# preparedinstruments_0_bechemel_v12_KEYPA.net
KiCad netlist of a schematic drawn in EAGLE
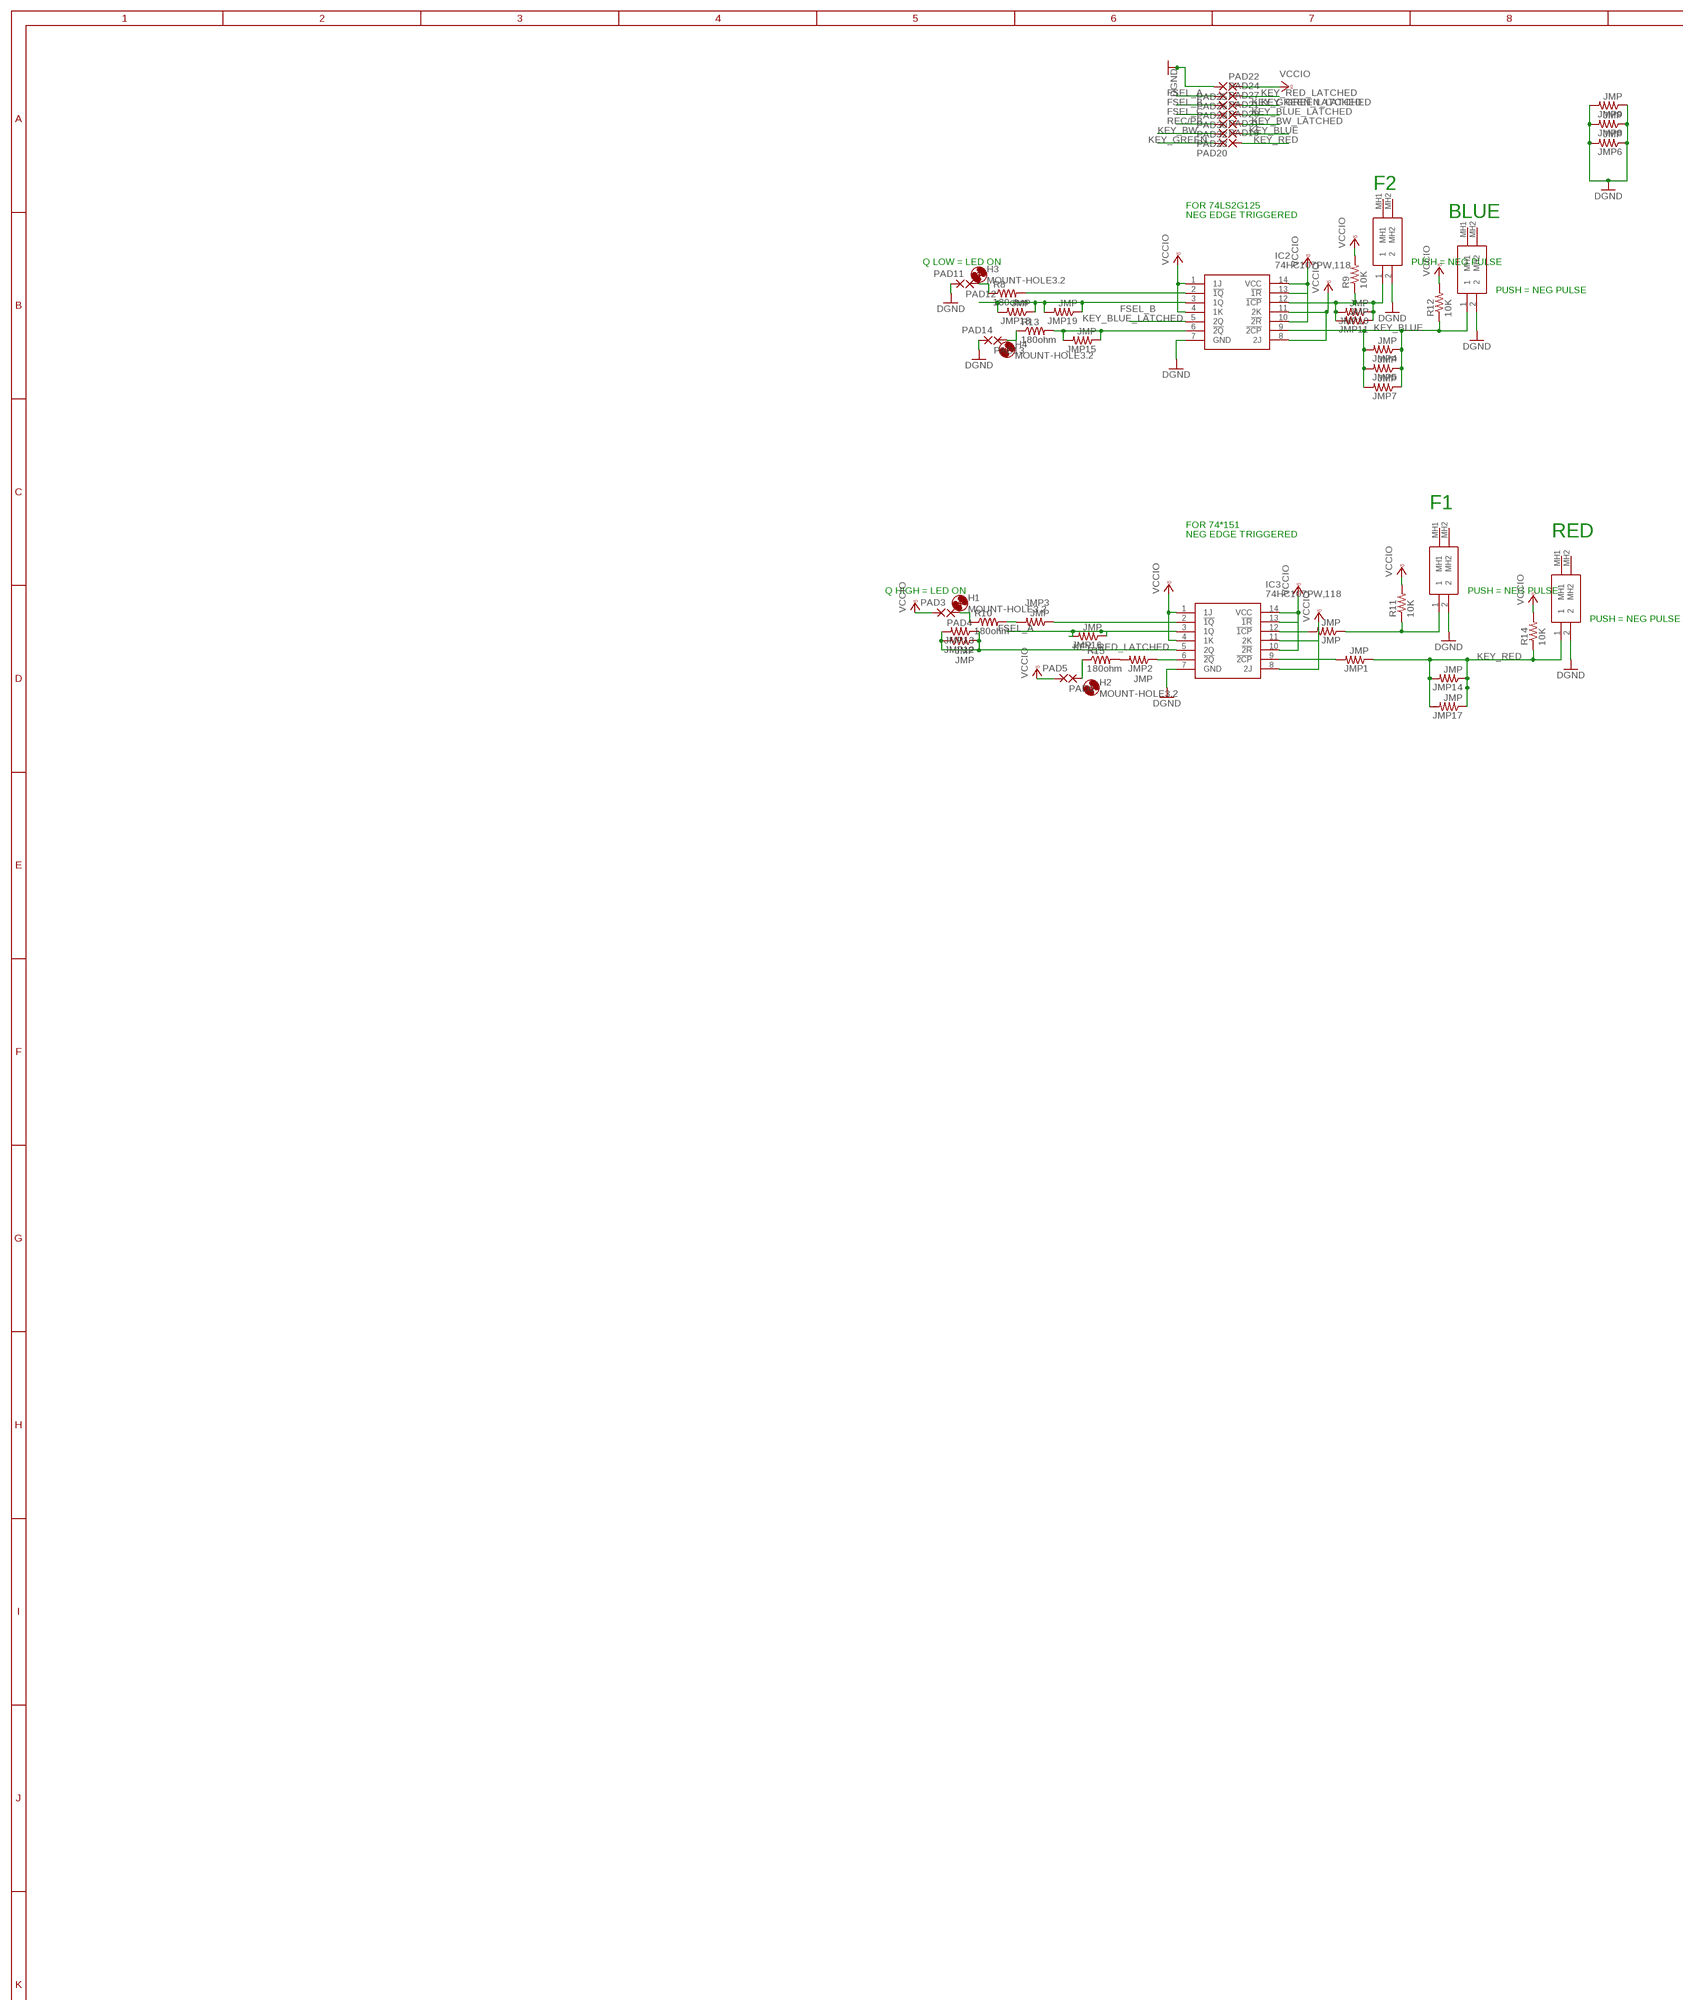
[diagram p0: schematic, sheet 1, part 1 of 3]
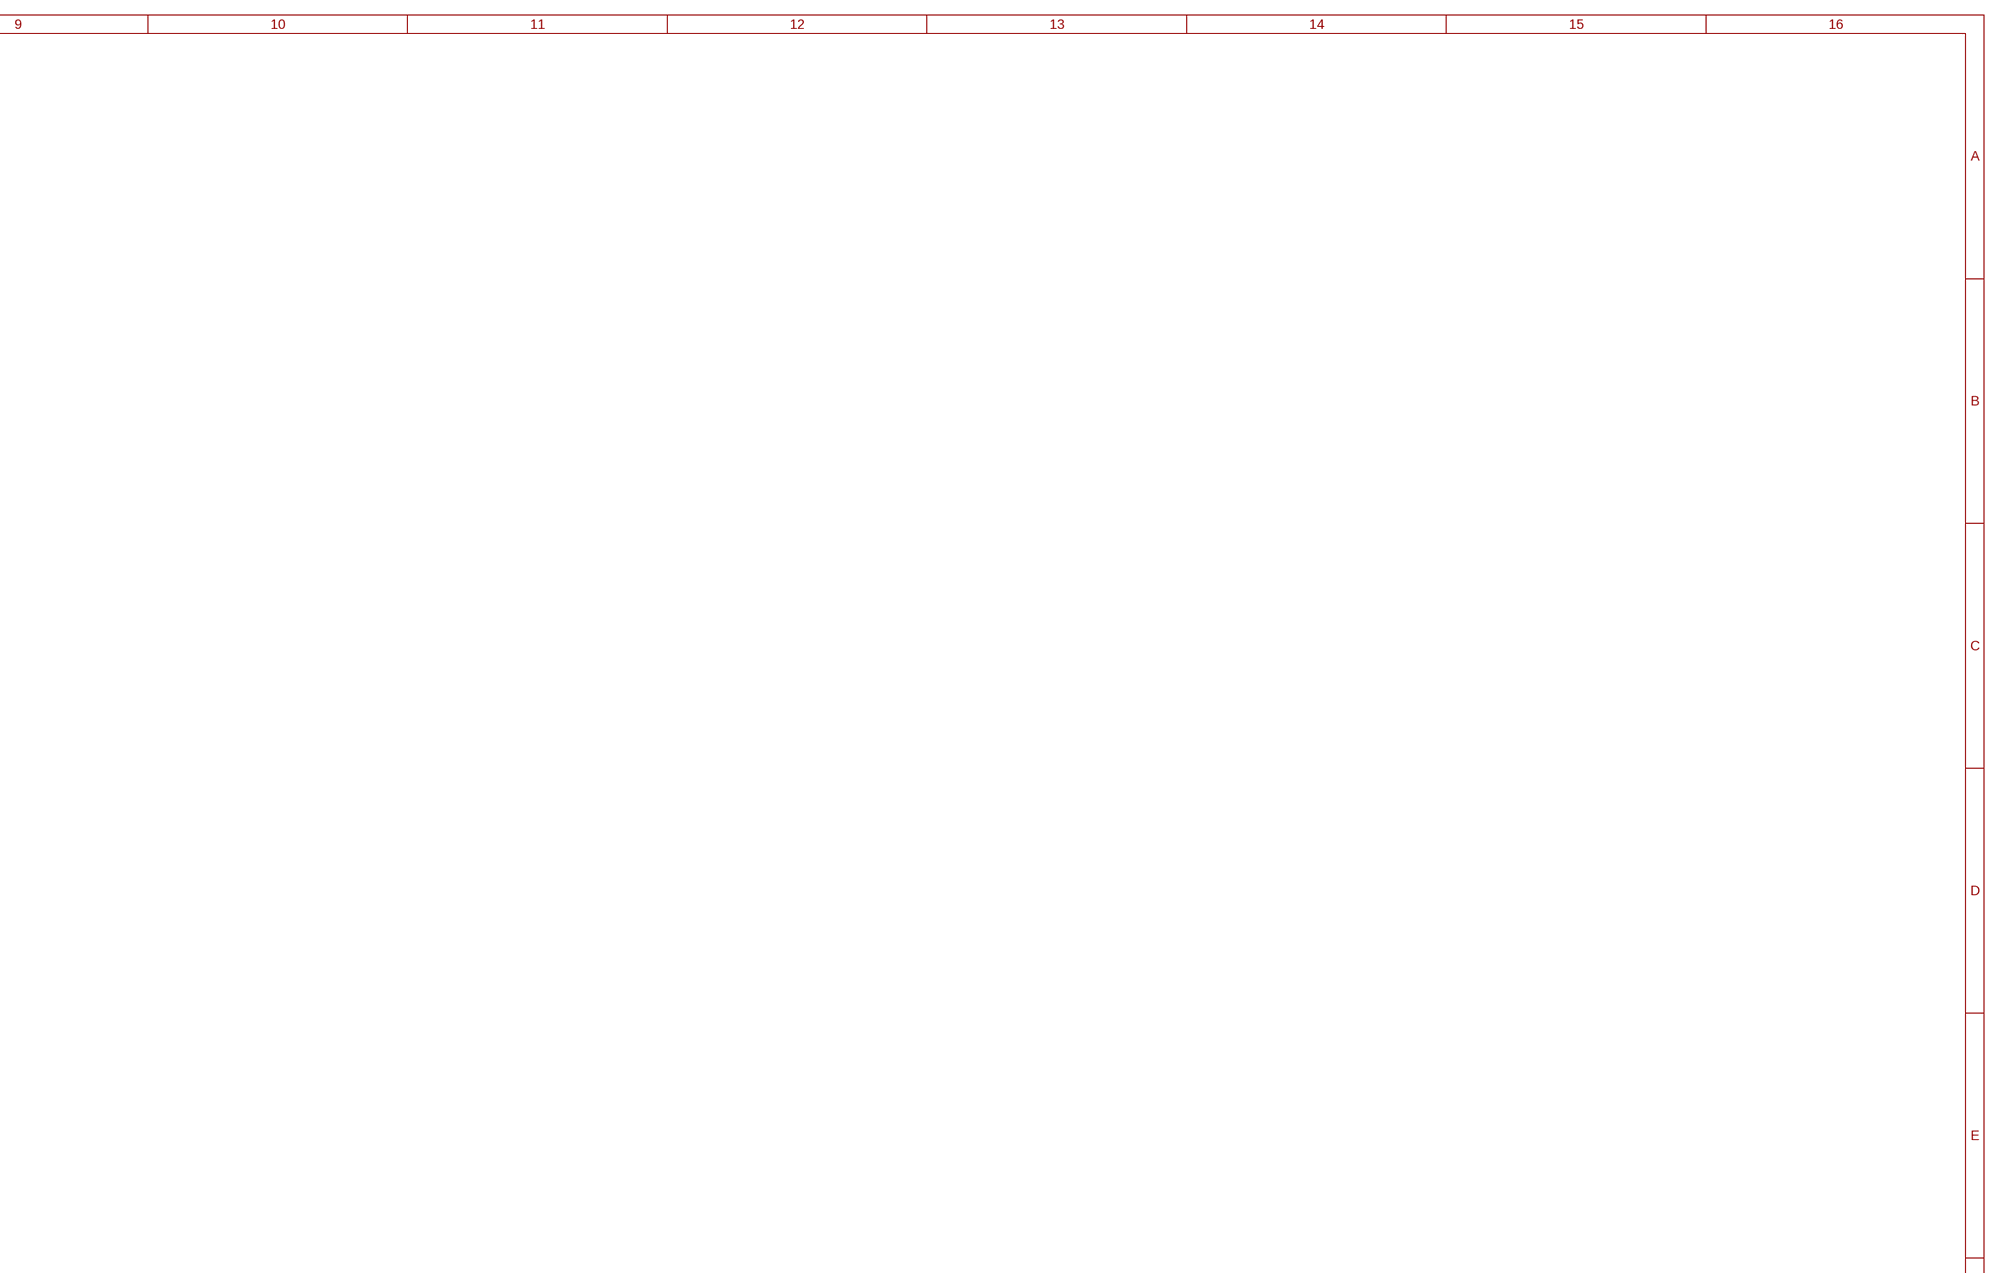
[diagram p1: schematic, sheet 1, part 2 of 3]
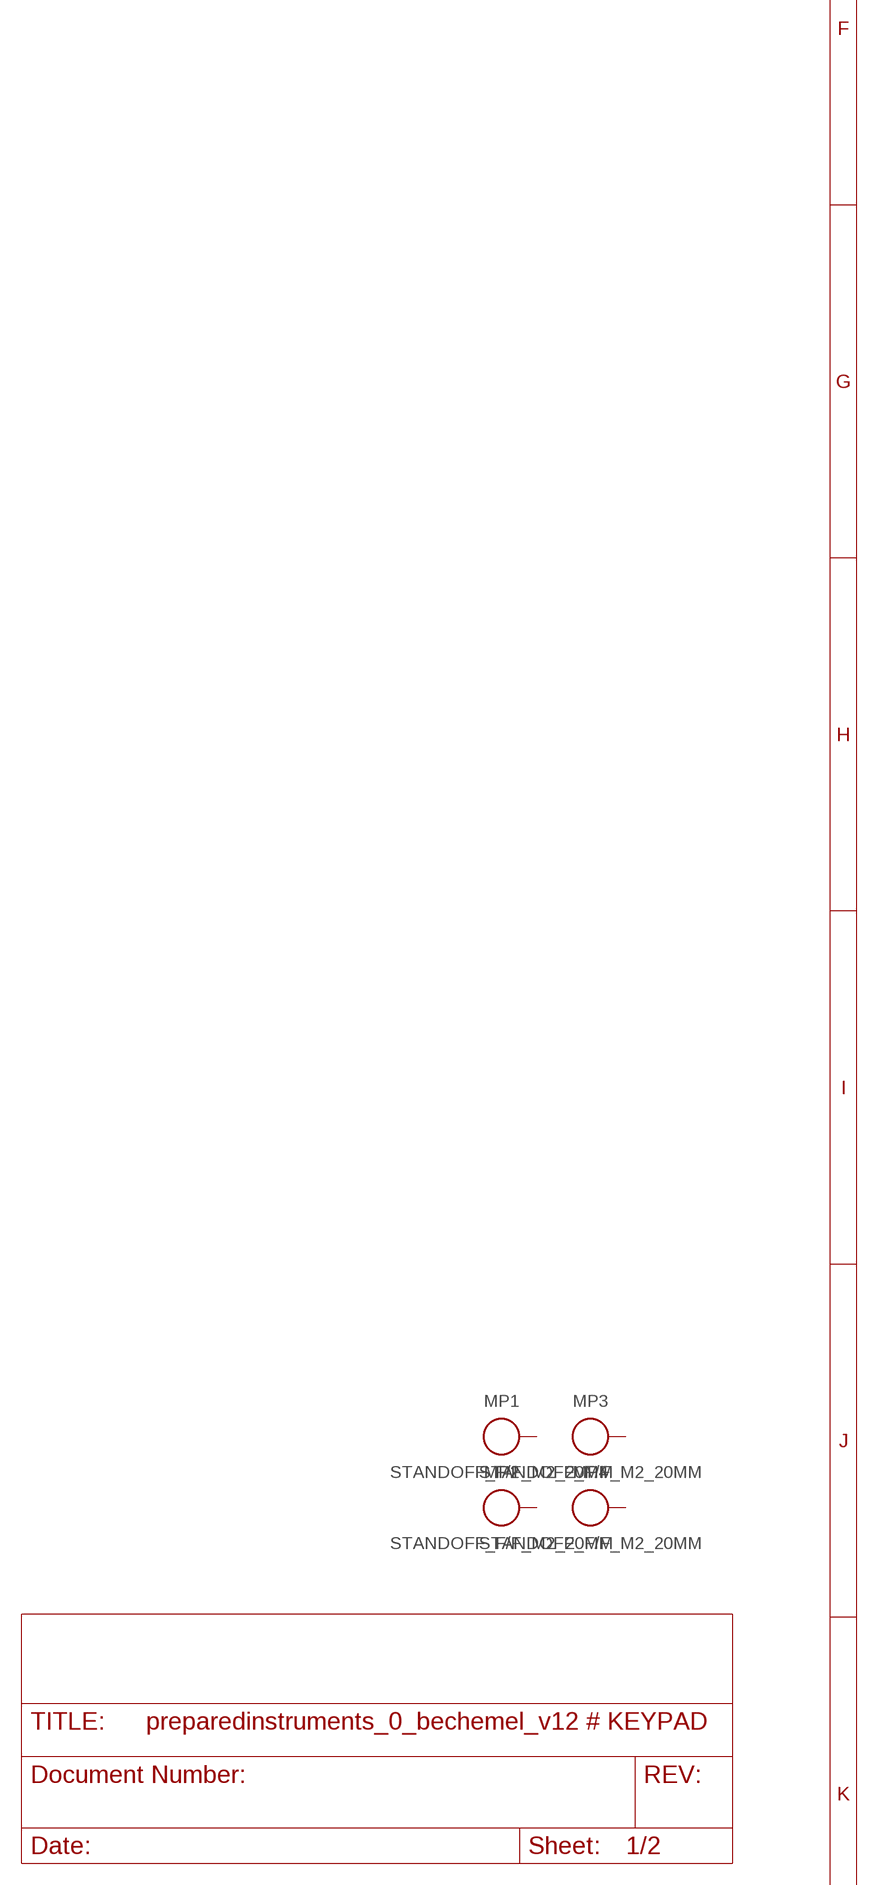
[diagram p2: schematic, sheet 1, part 3 of 3]
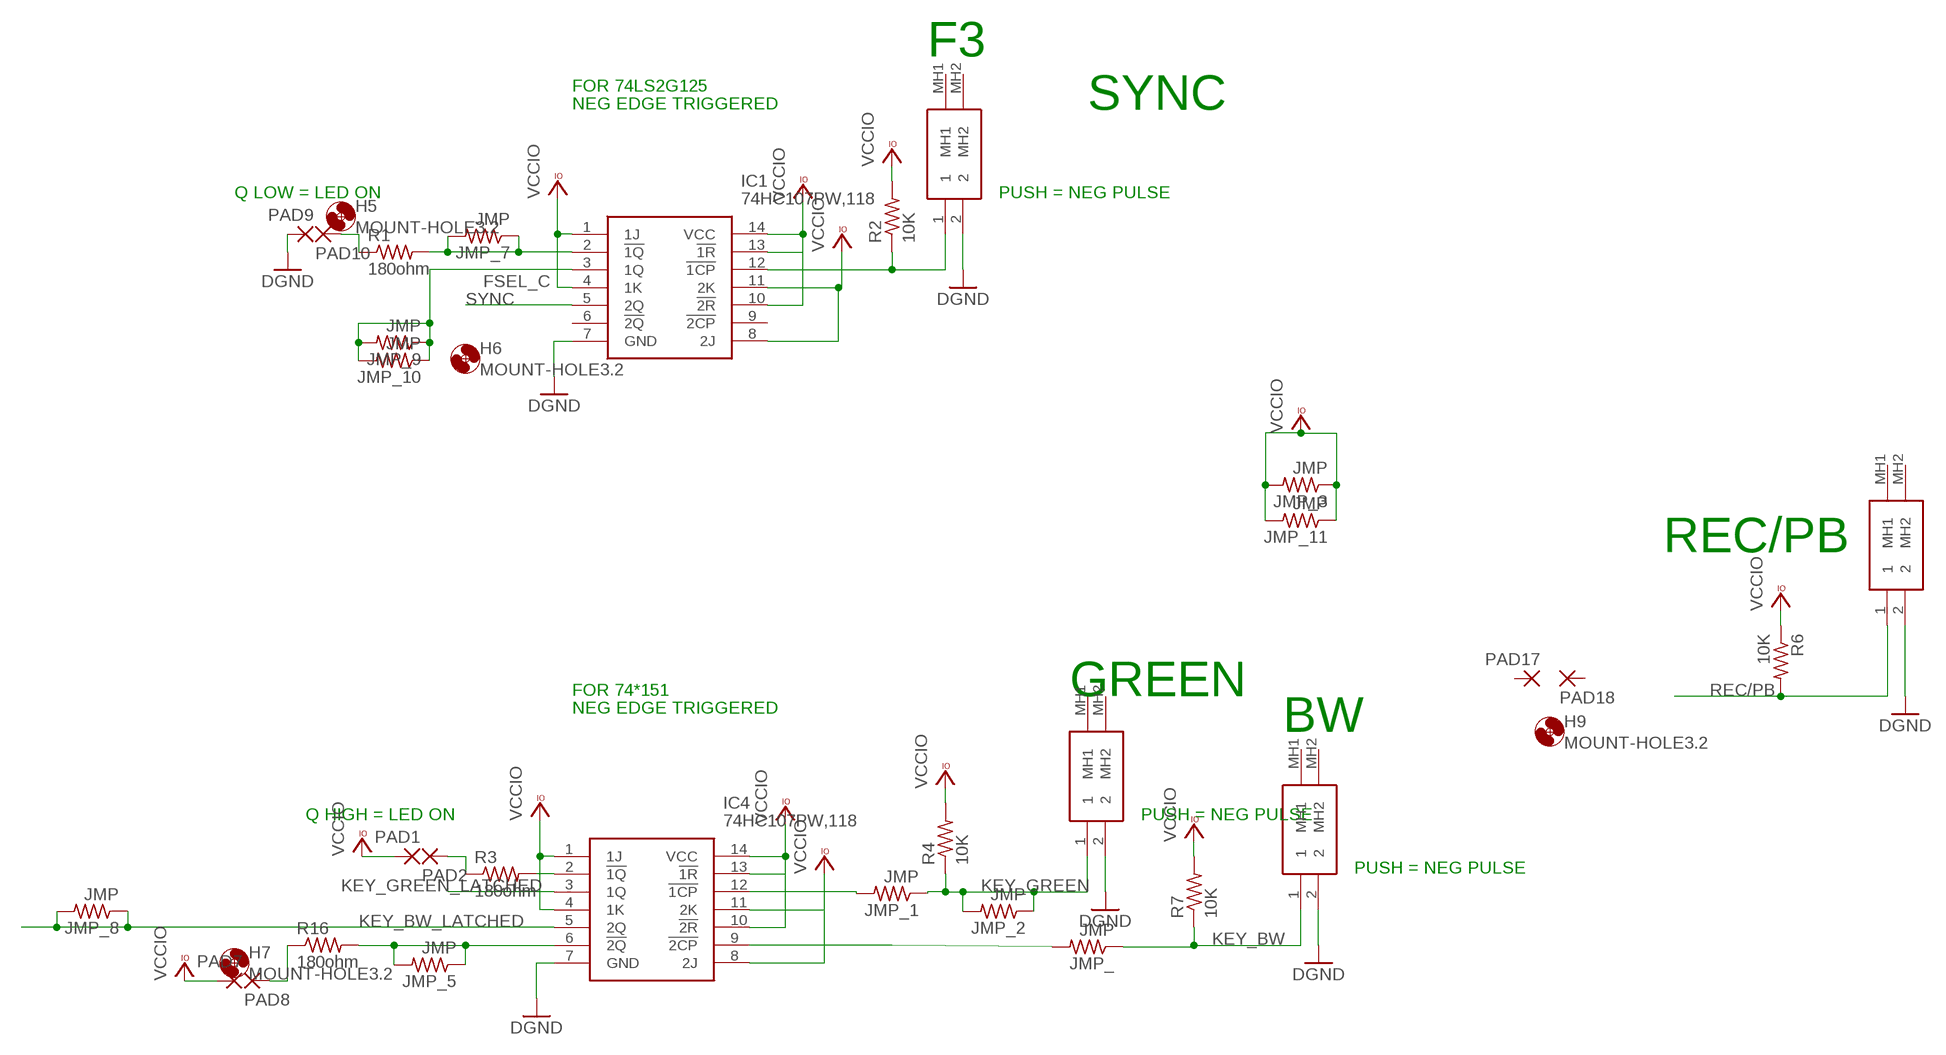
[diagram p3: schematic, sheet 2]

(export (version "E")
  (design (tool "Eeschema 10.0.6"))
  (components
    (comp (ref "H5")
      (value "MOUNT-HOLE3.2")
      (footprint "eagle-import:3,2")
      (libsource (lib "eagle-import") (part "MOUNT-HOLE3.2"))
    )
    (comp (ref "H6")
      (value "MOUNT-HOLE3.2")
      (footprint "eagle-import:3,2")
      (libsource (lib "eagle-import") (part "MOUNT-HOLE3.2"))
    )
    (comp (ref "H7")
      (value "MOUNT-HOLE3.2")
      (footprint "eagle-import:3,2")
      (libsource (lib "eagle-import") (part "MOUNT-HOLE3.2"))
    )
    (comp (ref "H9")
      (value "MOUNT-HOLE3.2")
      (footprint "eagle-import:3,2")
      (libsource (lib "eagle-import") (part "MOUNT-HOLE3.2"))
    )
    (comp (ref "IC1")
      (value "74HC107PW,118")
      (footprint "eagle-import:SOP65P640X110-14N")
      (fields (field (name "MOUSER_PART_NUMBER") "771-HC107PW118"))
      (libsource (lib "eagle-import") (part "74HC107PW,118"))
    )
    (comp (ref "IC4")
      (value "74HC107PW,118")
      (footprint "eagle-import:SOP65P640X110-14N")
      (fields (field (name "MOUSER_PART_NUMBER") "771-HC107PW118"))
      (libsource (lib "eagle-import") (part "74HC107PW,118"))
    )
    (comp (ref "JMP_")
      (value "JMP")
      (footprint "eagle-import:R0805")
      (libsource (lib "eagle-import") (part "R-US_R0805"))
    )
    (comp (ref "JMP_1")
      (value "JMP")
      (footprint "eagle-import:R0805")
      (libsource (lib "eagle-import") (part "R-US_R0805"))
    )
    (comp (ref "JMP_2")
      (value "JMP")
      (footprint "eagle-import:R0805")
      (libsource (lib "eagle-import") (part "R-US_R0805"))
    )
    (comp (ref "JMP_3")
      (value "JMP")
      (footprint "eagle-import:R0805")
      (libsource (lib "eagle-import") (part "R-US_R0805"))
    )
    (comp (ref "JMP_5")
      (value "JMP")
      (footprint "eagle-import:R0805")
      (libsource (lib "eagle-import") (part "R-US_R0805"))
    )
    (comp (ref "JMP_7")
      (value "JMP")
      (footprint "eagle-import:R0805")
      (libsource (lib "eagle-import") (part "R-US_R0805"))
    )
    (comp (ref "JMP_8")
      (value "JMP")
      (footprint "eagle-import:R0805")
      (libsource (lib "eagle-import") (part "R-US_R0805"))
    )
    (comp (ref "JMP_9")
      (value "JMP")
      (footprint "eagle-import:R0805")
      (libsource (lib "eagle-import") (part "R-US_R0805"))
    )
    (comp (ref "JMP_10")
      (value "JMP")
      (footprint "eagle-import:R0805")
      (libsource (lib "eagle-import") (part "R-US_R0805"))
    )
    (comp (ref "JMP_11")
      (value "JMP")
      (footprint "eagle-import:R0805")
      (libsource (lib "eagle-import") (part "R-US_R0805"))
    )
    (comp (ref "PAD1")
      (value "SMD2")
      (footprint "eagle-import:SMD1,27-2,54")
      (libsource (lib "eagle-import") (part "SMD2"))
    )
    (comp (ref "PAD2")
      (value "SMD2")
      (footprint "eagle-import:SMD1,27-2,54")
      (libsource (lib "eagle-import") (part "SMD2"))
    )
    (comp (ref "PAD7")
      (value "SMD2")
      (footprint "eagle-import:SMD1,27-2,54")
      (libsource (lib "eagle-import") (part "SMD2"))
    )
    (comp (ref "PAD8")
      (value "SMD2")
      (footprint "eagle-import:SMD1,27-2,54")
      (libsource (lib "eagle-import") (part "SMD2"))
    )
    (comp (ref "PAD9")
      (value "SMD2")
      (footprint "eagle-import:SMD1,27-2,54")
      (libsource (lib "eagle-import") (part "SMD2"))
    )
    (comp (ref "PAD10")
      (value "SMD2")
      (footprint "eagle-import:SMD1,27-2,54")
      (libsource (lib "eagle-import") (part "SMD2"))
    )
    (comp (ref "PAD17")
      (value "SMD2")
      (footprint "eagle-import:SMD1,27-2,54")
      (libsource (lib "eagle-import") (part "SMD2"))
    )
    (comp (ref "PAD18")
      (value "SMD2")
      (footprint "eagle-import:SMD1,27-2,54")
      (libsource (lib "eagle-import") (part "SMD2"))
    )
    (comp (ref "R1")
      (value "180ohm")
      (footprint "eagle-import:R0805")
      (libsource (lib "eagle-import") (part "R-US_R0805"))
    )
    (comp (ref "R2")
      (value "10K")
      (footprint "eagle-import:R0805")
      (libsource (lib "eagle-import") (part "R-US_R0805"))
    )
    (comp (ref "R3")
      (value "180ohm")
      (footprint "eagle-import:R0805")
      (libsource (lib "eagle-import") (part "R-US_R0805"))
    )
    (comp (ref "R4")
      (value "10K")
      (footprint "eagle-import:R0805")
      (libsource (lib "eagle-import") (part "R-US_R0805"))
    )
    (comp (ref "R6")
      (value "10K")
      (footprint "eagle-import:R0805")
      (libsource (lib "eagle-import") (part "R-US_R0805"))
    )
    (comp (ref "R7")
      (value "10K")
      (footprint "eagle-import:R0805")
      (libsource (lib "eagle-import") (part "R-US_R0805"))
    )
    (comp (ref "R16")
      (value "180ohm")
      (footprint "eagle-import:R0805")
      (libsource (lib "eagle-import") (part "R-US_R0805"))
    )
    (comp (ref "S1")
      (value "MX1A-11NW")
      (footprint "eagle-import:MX1A11NW")
      (fields (field (name "MOUSER_PART_NUMBER") "540-MX1A-11NW"))
      (libsource (lib "eagle-import") (part "MX1A-11NW"))
    )
    (comp (ref "S2")
      (value "MX1A-11NW")
      (footprint "eagle-import:MX1A11NW")
      (fields (field (name "MOUSER_PART_NUMBER") "540-MX1A-11NW"))
      (libsource (lib "eagle-import") (part "MX1A-11NW"))
    )
    (comp (ref "S4")
      (value "MX1A-11NW")
      (footprint "eagle-import:MX1A11NW")
      (fields (field (name "MOUSER_PART_NUMBER") "540-MX1A-11NW"))
      (libsource (lib "eagle-import") (part "MX1A-11NW"))
    )
    (comp (ref "S5")
      (value "MX1A-11NW")
      (footprint "eagle-import:MX1A11NW")
      (fields (field (name "MOUSER_PART_NUMBER") "540-MX1A-11NW"))
      (libsource (lib "eagle-import") (part "MX1A-11NW"))
    )
    (comp (ref "H1")
      (value "MOUNT-HOLE3.2")
      (footprint "eagle-import:3,2")
      (libsource (lib "eagle-import") (part "MOUNT-HOLE3.2"))
    )
    (comp (ref "H2")
      (value "MOUNT-HOLE3.2")
      (footprint "eagle-import:3,2")
      (libsource (lib "eagle-import") (part "MOUNT-HOLE3.2"))
    )
    (comp (ref "H3")
      (value "MOUNT-HOLE3.2")
      (footprint "eagle-import:3,2")
      (libsource (lib "eagle-import") (part "MOUNT-HOLE3.2"))
    )
    (comp (ref "H4")
      (value "MOUNT-HOLE3.2")
      (footprint "eagle-import:3,2")
      (libsource (lib "eagle-import") (part "MOUNT-HOLE3.2"))
    )
    (comp (ref "IC2")
      (value "74HC107PW,118")
      (footprint "eagle-import:SOP65P640X110-14N")
      (fields (field (name "MOUSER_PART_NUMBER") "771-HC107PW118"))
      (libsource (lib "eagle-import") (part "74HC107PW,118"))
    )
    (comp (ref "IC3")
      (value "74HC107PW,118")
      (footprint "eagle-import:SOP65P640X110-14N")
      (fields (field (name "MOUSER_PART_NUMBER") "771-HC107PW118"))
      (libsource (lib "eagle-import") (part "74HC107PW,118"))
    )
    (comp (ref "JMP")
      (value "JMP")
      (footprint "eagle-import:R0805")
      (libsource (lib "eagle-import") (part "R-US_R0805"))
    )
    (comp (ref "JMP1")
      (value "JMP")
      (footprint "eagle-import:R0805")
      (libsource (lib "eagle-import") (part "R-US_R0805"))
    )
    (comp (ref "JMP2")
      (value "JMP")
      (footprint "eagle-import:R0805")
      (libsource (lib "eagle-import") (part "R-US_R0805"))
    )
    (comp (ref "JMP3")
      (value "JMP")
      (footprint "eagle-import:R0805")
      (libsource (lib "eagle-import") (part "R-US_R0805"))
    )
    (comp (ref "JMP4")
      (value "JMP")
      (footprint "eagle-import:R0805")
      (libsource (lib "eagle-import") (part "R-US_R0805"))
    )
    (comp (ref "JMP5")
      (value "JMP")
      (footprint "eagle-import:R0805")
      (libsource (lib "eagle-import") (part "R-US_R0805"))
    )
    (comp (ref "JMP6")
      (value "JMP")
      (footprint "eagle-import:R0805")
      (libsource (lib "eagle-import") (part "R-US_R0805"))
    )
    (comp (ref "JMP7")
      (value "JMP")
      (footprint "eagle-import:R0805")
      (libsource (lib "eagle-import") (part "R-US_R0805"))
    )
    (comp (ref "JMP8")
      (value "JMP")
      (footprint "eagle-import:R0805")
      (libsource (lib "eagle-import") (part "R-US_R0805"))
    )
    (comp (ref "JMP9")
      (value "JMP")
      (footprint "eagle-import:R0805")
      (libsource (lib "eagle-import") (part "R-US_R0805"))
    )
    (comp (ref "JMP10")
      (value "JMP")
      (footprint "eagle-import:R0805")
      (libsource (lib "eagle-import") (part "R-US_R0805"))
    )
    (comp (ref "JMP11")
      (value "JMP")
      (footprint "eagle-import:R0805")
      (libsource (lib "eagle-import") (part "R-US_R0805"))
    )
    (comp (ref "JMP12")
      (value "JMP")
      (footprint "eagle-import:R0805")
      (libsource (lib "eagle-import") (part "R-US_R0805"))
    )
    (comp (ref "JMP13")
      (value "JMP")
      (footprint "eagle-import:R0805")
      (libsource (lib "eagle-import") (part "R-US_R0805"))
    )
    (comp (ref "JMP14")
      (value "JMP")
      (footprint "eagle-import:R0805")
      (libsource (lib "eagle-import") (part "R-US_R0805"))
    )
    (comp (ref "JMP15")
      (value "JMP")
      (footprint "eagle-import:R0805")
      (libsource (lib "eagle-import") (part "R-US_R0805"))
    )
    (comp (ref "JMP16")
      (value "JMP")
      (footprint "eagle-import:R0805")
      (libsource (lib "eagle-import") (part "R-US_R0805"))
    )
    (comp (ref "JMP17")
      (value "JMP")
      (footprint "eagle-import:R0805")
      (libsource (lib "eagle-import") (part "R-US_R0805"))
    )
    (comp (ref "JMP18")
      (value "JMP")
      (footprint "eagle-import:R0805")
      (libsource (lib "eagle-import") (part "R-US_R0805"))
    )
    (comp (ref "JMP19")
      (value "JMP")
      (footprint "eagle-import:R0805")
      (libsource (lib "eagle-import") (part "R-US_R0805"))
    )
    (comp (ref "MP1")
      (value "STANDOFF_F/F_M2_20MM")
      (footprint "eagle-import:STANDOFF_HEX_FEMALE_400X2000_M2X0.4_MTGP600H220")
      (libsource (lib "eagle-import") (part "STANDOFF_F/FM2_20MM_"))
    )
    (comp (ref "MP2")
      (value "STANDOFF_F/F_M2_20MM")
      (footprint "eagle-import:STANDOFF_HEX_FEMALE_400X2000_M2X0.4_MTGP600H220")
      (libsource (lib "eagle-import") (part "STANDOFF_F/FM2_20MM_"))
    )
    (comp (ref "MP3")
      (value "STANDOFF_F/F_M2_20MM")
      (footprint "eagle-import:STANDOFF_HEX_FEMALE_400X2000_M2X0.4_MTGP600H220")
      (libsource (lib "eagle-import") (part "STANDOFF_F/FM2_20MM_"))
    )
    (comp (ref "MP4")
      (value "STANDOFF_F/F_M2_20MM")
      (footprint "eagle-import:STANDOFF_HEX_FEMALE_400X2000_M2X0.4_MTGP600H220")
      (libsource (lib "eagle-import") (part "STANDOFF_F/FM2_20MM_"))
    )
    (comp (ref "PAD3")
      (value "SMD2")
      (footprint "eagle-import:SMD1,27-2,54")
      (libsource (lib "eagle-import") (part "SMD2"))
    )
    (comp (ref "PAD4")
      (value "SMD2")
      (footprint "eagle-import:SMD1,27-2,54")
      (libsource (lib "eagle-import") (part "SMD2"))
    )
    (comp (ref "PAD5")
      (value "SMD2")
      (footprint "eagle-import:SMD1,27-2,54")
      (libsource (lib "eagle-import") (part "SMD2"))
    )
    (comp (ref "PAD6")
      (value "SMD2")
      (footprint "eagle-import:SMD1,27-2,54")
      (libsource (lib "eagle-import") (part "SMD2"))
    )
    (comp (ref "PAD11")
      (value "SMD2")
      (footprint "eagle-import:SMD1,27-2,54")
      (libsource (lib "eagle-import") (part "SMD2"))
    )
    (comp (ref "PAD12")
      (value "SMD2")
      (footprint "eagle-import:SMD1,27-2,54")
      (libsource (lib "eagle-import") (part "SMD2"))
    )
    (comp (ref "PAD13")
      (value "SMD2")
      (footprint "eagle-import:SMD1,27-2,54")
      (libsource (lib "eagle-import") (part "SMD2"))
    )
    (comp (ref "PAD14")
      (value "SMD2")
      (footprint "eagle-import:SMD1,27-2,54")
      (libsource (lib "eagle-import") (part "SMD2"))
    )
    (comp (ref "PAD19")
      (value "SMD2")
      (footprint "eagle-import:SMD1,27-2,54")
      (libsource (lib "eagle-import") (part "SMD2"))
    )
    (comp (ref "PAD20")
      (value "SMD2")
      (footprint "eagle-import:SMD1,27-2,54")
      (libsource (lib "eagle-import") (part "SMD2"))
    )
    (comp (ref "PAD21")
      (value "SMD2")
      (footprint "eagle-import:SMD1,27-2,54")
      (libsource (lib "eagle-import") (part "SMD2"))
    )
    (comp (ref "PAD22")
      (value "SMD2")
      (footprint "eagle-import:SMD1,27-2,54")
      (libsource (lib "eagle-import") (part "SMD2"))
    )
    (comp (ref "PAD23")
      (value "SMD2")
      (footprint "eagle-import:SMD1,27-2,54")
      (libsource (lib "eagle-import") (part "SMD2"))
    )
    (comp (ref "PAD24")
      (value "SMD2")
      (footprint "eagle-import:SMD1,27-2,54")
      (libsource (lib "eagle-import") (part "SMD2"))
    )
    (comp (ref "PAD25")
      (value "SMD2")
      (footprint "eagle-import:SMD1,27-2,54")
      (libsource (lib "eagle-import") (part "SMD2"))
    )
    (comp (ref "PAD26")
      (value "SMD2")
      (footprint "eagle-import:SMD1,27-2,54")
      (libsource (lib "eagle-import") (part "SMD2"))
    )
    (comp (ref "PAD27")
      (value "SMD2")
      (footprint "eagle-import:SMD1,27-2,54")
      (libsource (lib "eagle-import") (part "SMD2"))
    )
    (comp (ref "PAD28")
      (value "SMD2")
      (footprint "eagle-import:SMD1,27-2,54")
      (libsource (lib "eagle-import") (part "SMD2"))
    )
    (comp (ref "PAD29")
      (value "SMD2")
      (footprint "eagle-import:SMD1,27-2,54")
      (libsource (lib "eagle-import") (part "SMD2"))
    )
    (comp (ref "PAD30")
      (value "SMD2")
      (footprint "eagle-import:SMD1,27-2,54")
      (libsource (lib "eagle-import") (part "SMD2"))
    )
    (comp (ref "PAD31")
      (value "SMD2")
      (footprint "eagle-import:SMD1,27-2,54")
      (libsource (lib "eagle-import") (part "SMD2"))
    )
    (comp (ref "PAD32")
      (value "SMD2")
      (footprint "eagle-import:SMD1,27-2,54")
      (libsource (lib "eagle-import") (part "SMD2"))
    )
    (comp (ref "R8")
      (value "180ohm")
      (footprint "eagle-import:R0805")
      (libsource (lib "eagle-import") (part "R-US_R0805"))
    )
    (comp (ref "R9")
      (value "10K")
      (footprint "eagle-import:R0805")
      (libsource (lib "eagle-import") (part "R-US_R0805"))
    )
    (comp (ref "R10")
      (value "180ohm")
      (footprint "eagle-import:R0805")
      (libsource (lib "eagle-import") (part "R-US_R0805"))
    )
    (comp (ref "R11")
      (value "10K")
      (footprint "eagle-import:R0805")
      (libsource (lib "eagle-import") (part "R-US_R0805"))
    )
    (comp (ref "R12")
      (value "10K")
      (footprint "eagle-import:R0805")
      (libsource (lib "eagle-import") (part "R-US_R0805"))
    )
    (comp (ref "R13")
      (value "180ohm")
      (footprint "eagle-import:R0805")
      (libsource (lib "eagle-import") (part "R-US_R0805"))
    )
    (comp (ref "R14")
      (value "10K")
      (footprint "eagle-import:R0805")
      (libsource (lib "eagle-import") (part "R-US_R0805"))
    )
    (comp (ref "R15")
      (value "180ohm")
      (footprint "eagle-import:R0805")
      (libsource (lib "eagle-import") (part "R-US_R0805"))
    )
    (comp (ref "S6")
      (value "MX1A-11NW")
      (footprint "eagle-import:MX1A11NW")
      (fields (field (name "MOUSER_PART_NUMBER") "540-MX1A-11NW"))
      (libsource (lib "eagle-import") (part "MX1A-11NW"))
    )
    (comp (ref "S7")
      (value "MX1A-11NW")
      (footprint "eagle-import:MX1A11NW")
      (fields (field (name "MOUSER_PART_NUMBER") "540-MX1A-11NW"))
      (libsource (lib "eagle-import") (part "MX1A-11NW"))
    )
    (comp (ref "S8")
      (value "MX1A-11NW")
      (footprint "eagle-import:MX1A11NW")
      (fields (field (name "MOUSER_PART_NUMBER") "540-MX1A-11NW"))
      (libsource (lib "eagle-import") (part "MX1A-11NW"))
    )
    (comp (ref "S9")
      (value "MX1A-11NW")
      (footprint "eagle-import:MX1A11NW")
      (fields (field (name "MOUSER_PART_NUMBER") "540-MX1A-11NW"))
      (libsource (lib "eagle-import") (part "MX1A-11NW"))
    )
  )
  (nets
    (net (code "1") (name "DGND") (class "Default")
      (node (ref "IC1") (pin "7") (pinfunction "GND_7") (pintype "bidirectional"))
      (node (ref "IC2") (pin "7") (pinfunction "GND_7") (pintype "bidirectional"))
      (node (ref "IC3") (pin "7") (pinfunction "GND_7") (pintype "bidirectional"))
      (node (ref "IC4") (pin "7") (pinfunction "GND_7") (pintype "bidirectional"))
      (node (ref "JMP6") (pin "1") (pinfunction "1_1") (pintype "passive"))
      (node (ref "JMP6") (pin "2") (pinfunction "2_2") (pintype "passive"))
      (node (ref "JMP8") (pin "1") (pinfunction "1_1") (pintype "passive"))
      (node (ref "JMP8") (pin "2") (pinfunction "2_2") (pintype "passive"))
      (node (ref "JMP9") (pin "1") (pinfunction "1_1") (pintype "passive"))
      (node (ref "JMP9") (pin "2") (pinfunction "2_2") (pintype "passive"))
      (node (ref "PAD11") (pin "1") (pinfunction "P_1") (pintype "passive"))
      (node (ref "PAD14") (pin "1") (pinfunction "P_1") (pintype "passive"))
      (node (ref "PAD25") (pin "1") (pinfunction "P_1") (pintype "passive"))
      (node (ref "PAD9") (pin "1") (pinfunction "P_1") (pintype "passive"))
      (node (ref "S1") (pin "2") (pinfunction "2_2") (pintype "bidirectional"))
      (node (ref "S2") (pin "2") (pinfunction "2_2") (pintype "bidirectional"))
      (node (ref "S4") (pin "2") (pinfunction "2_2") (pintype "bidirectional"))
      (node (ref "S5") (pin "2") (pinfunction "2_2") (pintype "bidirectional"))
      (node (ref "S6") (pin "2") (pinfunction "2_2") (pintype "bidirectional"))
      (node (ref "S7") (pin "2") (pinfunction "2_2") (pintype "bidirectional"))
      (node (ref "S8") (pin "2") (pinfunction "2_2") (pintype "bidirectional"))
      (node (ref "S9") (pin "2") (pinfunction "2_2") (pintype "bidirectional"))
    )
    (net (code "2") (name "FSEL_A") (class "Default")
      (node (ref "IC3") (pin "3") (pinfunction "1Q_3") (pintype "bidirectional"))
      (node (ref "JMP16") (pin "1") (pinfunction "1_1") (pintype "passive"))
      (node (ref "JMP16") (pin "2") (pinfunction "2_2") (pintype "passive"))
      (node (ref "PAD26") (pin "1") (pinfunction "P_1") (pintype "passive"))
    )
    (net (code "3") (name "FSEL_B") (class "Default")
      (node (ref "IC2") (pin "3") (pinfunction "1Q_3") (pintype "bidirectional"))
      (node (ref "JMP18") (pin "1") (pinfunction "1_1") (pintype "passive"))
      (node (ref "JMP18") (pin "2") (pinfunction "2_2") (pintype "passive"))
      (node (ref "JMP19") (pin "1") (pinfunction "1_1") (pintype "passive"))
      (node (ref "JMP19") (pin "2") (pinfunction "2_2") (pintype "passive"))
      (node (ref "PAD28") (pin "1") (pinfunction "P_1") (pintype "passive"))
    )
    (net (code "4") (name "FSEL_C") (class "Default")
      (node (ref "IC1") (pin "3") (pinfunction "1Q_3") (pintype "bidirectional"))
      (node (ref "JMP_10") (pin "1") (pinfunction "1_1") (pintype "passive"))
      (node (ref "JMP_10") (pin "2") (pinfunction "2_2") (pintype "passive"))
      (node (ref "JMP_9") (pin "1") (pinfunction "1_1") (pintype "passive"))
      (node (ref "JMP_9") (pin "2") (pinfunction "2_2") (pintype "passive"))
      (node (ref "PAD30") (pin "1") (pinfunction "P_1") (pintype "passive"))
    )
    (net (code "5") (name "KEY_BLUE") (class "Default")
      (node (ref "IC2") (pin "9") (pinfunction "~{2CP}_9") (pintype "bidirectional"))
      (node (ref "JMP4") (pin "1") (pinfunction "1_1") (pintype "passive"))
      (node (ref "JMP4") (pin "2") (pinfunction "2_2") (pintype "passive"))
      (node (ref "JMP5") (pin "1") (pinfunction "1_1") (pintype "passive"))
      (node (ref "JMP5") (pin "2") (pinfunction "2_2") (pintype "passive"))
      (node (ref "JMP7") (pin "1") (pinfunction "1_1") (pintype "passive"))
      (node (ref "JMP7") (pin "2") (pinfunction "2_2") (pintype "passive"))
      (node (ref "PAD31") (pin "1") (pinfunction "P_1") (pintype "passive"))
      (node (ref "R12") (pin "1") (pinfunction "1_1") (pintype "passive"))
      (node (ref "S8") (pin "1") (pinfunction "1_1") (pintype "bidirectional"))
    )
    (net (code "6") (name "KEY_BLUE_LATCHED") (class "Default")
      (node (ref "IC2") (pin "5") (pinfunction "2Q_5") (pintype "bidirectional"))
      (node (ref "PAD21") (pin "1") (pinfunction "P_1") (pintype "passive"))
    )
    (net (code "7") (name "KEY_BW") (class "Default")
      (node (ref "JMP_") (pin "1") (pinfunction "1_1") (pintype "passive"))
      (node (ref "PAD23") (pin "1") (pinfunction "P_1") (pintype "passive"))
      (node (ref "R7") (pin "1") (pinfunction "1_1") (pintype "passive"))
      (node (ref "S4") (pin "1") (pinfunction "1_1") (pintype "bidirectional"))
    )
    (net (code "8") (name "KEY_BW_LATCHED") (class "Default")
      (node (ref "IC4") (pin "5") (pinfunction "2Q_5") (pintype "bidirectional"))
      (node (ref "JMP_8") (pin "1") (pinfunction "1_1") (pintype "passive"))
      (node (ref "JMP_8") (pin "2") (pinfunction "2_2") (pintype "passive"))
      (node (ref "PAD29") (pin "1") (pinfunction "P_1") (pintype "passive"))
    )
    (net (code "9") (name "KEY_GREEN") (class "Default")
      (node (ref "JMP_1") (pin "1") (pinfunction "1_1") (pintype "passive"))
      (node (ref "JMP_2") (pin "1") (pinfunction "1_1") (pintype "passive"))
      (node (ref "JMP_2") (pin "2") (pinfunction "2_2") (pintype "passive"))
      (node (ref "PAD20") (pin "1") (pinfunction "P_1") (pintype "passive"))
      (node (ref "R4") (pin "1") (pinfunction "1_1") (pintype "passive"))
      (node (ref "S2") (pin "1") (pinfunction "1_1") (pintype "bidirectional"))
    )
    (net (code "10") (name "KEY_GREEN_LATCHED") (class "Default")
      (node (ref "IC4") (pin "3") (pinfunction "1Q_3") (pintype "bidirectional"))
      (node (ref "PAD27") (pin "1") (pinfunction "P_1") (pintype "passive"))
    )
    (net (code "11") (name "KEY_RED") (class "Default")
      (node (ref "JMP1") (pin "1") (pinfunction "1_1") (pintype "passive"))
      (node (ref "JMP14") (pin "1") (pinfunction "1_1") (pintype "passive"))
      (node (ref "JMP14") (pin "2") (pinfunction "2_2") (pintype "passive"))
      (node (ref "JMP17") (pin "1") (pinfunction "1_1") (pintype "passive"))
      (node (ref "JMP17") (pin "2") (pinfunction "2_2") (pintype "passive"))
      (node (ref "PAD19") (pin "1") (pinfunction "P_1") (pintype "passive"))
      (node (ref "R14") (pin "1") (pinfunction "1_1") (pintype "passive"))
      (node (ref "S9") (pin "1") (pinfunction "1_1") (pintype "bidirectional"))
    )
    (net (code "12") (name "KEY_RED_LATCHED") (class "Default")
      (node (ref "IC3") (pin "5") (pinfunction "2Q_5") (pintype "bidirectional"))
      (node (ref "JMP12") (pin "1") (pinfunction "1_1") (pintype "passive"))
      (node (ref "JMP12") (pin "2") (pinfunction "2_2") (pintype "passive"))
      (node (ref "JMP13") (pin "1") (pinfunction "1_1") (pintype "passive"))
      (node (ref "JMP13") (pin "2") (pinfunction "2_2") (pintype "passive"))
      (node (ref "PAD24") (pin "1") (pinfunction "P_1") (pintype "passive"))
    )
    (net (code "13") (name "Net-(IC1-~{1CP})") (class "Default")
      (node (ref "IC1") (pin "12") (pinfunction "~{1CP}_12") (pintype "bidirectional"))
      (node (ref "R2") (pin "1") (pinfunction "1_1") (pintype "passive"))
      (node (ref "S1") (pin "1") (pinfunction "1_1") (pintype "bidirectional"))
    )
    (net (code "14") (name "Net-(IC1-~{1Q})") (class "Default")
      (node (ref "IC1") (pin "2") (pinfunction "~{1Q}_2") (pintype "bidirectional"))
      (node (ref "JMP_7") (pin "1") (pinfunction "1_1") (pintype "passive"))
      (node (ref "JMP_7") (pin "2") (pinfunction "2_2") (pintype "passive"))
      (node (ref "R1") (pin "2") (pinfunction "2_2") (pintype "passive"))
    )
    (net (code "15") (name "Net-(IC2-~{1CP})") (class "Default")
      (node (ref "IC2") (pin "12") (pinfunction "~{1CP}_12") (pintype "bidirectional"))
      (node (ref "JMP10") (pin "1") (pinfunction "1_1") (pintype "passive"))
      (node (ref "JMP10") (pin "2") (pinfunction "2_2") (pintype "passive"))
      (node (ref "JMP11") (pin "1") (pinfunction "1_1") (pintype "passive"))
      (node (ref "JMP11") (pin "2") (pinfunction "2_2") (pintype "passive"))
      (node (ref "R9") (pin "1") (pinfunction "1_1") (pintype "passive"))
      (node (ref "S6") (pin "1") (pinfunction "1_1") (pintype "bidirectional"))
    )
    (net (code "16") (name "Net-(IC2-~{1Q})") (class "Default")
      (node (ref "IC2") (pin "2") (pinfunction "~{1Q}_2") (pintype "bidirectional"))
      (node (ref "R8") (pin "2") (pinfunction "2_2") (pintype "passive"))
    )
    (net (code "17") (name "Net-(IC2-~{2Q})") (class "Default")
      (node (ref "IC2") (pin "6") (pinfunction "~{2Q}_6") (pintype "bidirectional"))
      (node (ref "JMP15") (pin "1") (pinfunction "1_1") (pintype "passive"))
      (node (ref "JMP15") (pin "2") (pinfunction "2_2") (pintype "passive"))
      (node (ref "R13") (pin "2") (pinfunction "2_2") (pintype "passive"))
    )
    (net (code "18") (name "Net-(IC3-~{1CP})") (class "Default")
      (node (ref "IC3") (pin "12") (pinfunction "~{1CP}_12") (pintype "bidirectional"))
      (node (ref "JMP") (pin "2") (pinfunction "2_2") (pintype "passive"))
    )
    (net (code "19") (name "Net-(IC3-~{1Q})") (class "Default")
      (node (ref "IC3") (pin "2") (pinfunction "~{1Q}_2") (pintype "bidirectional"))
      (node (ref "JMP3") (pin "1") (pinfunction "1_1") (pintype "passive"))
    )
    (net (code "20") (name "Net-(IC3-~{2CP})") (class "Default")
      (node (ref "IC3") (pin "9") (pinfunction "~{2CP}_9") (pintype "bidirectional"))
      (node (ref "JMP1") (pin "2") (pinfunction "2_2") (pintype "passive"))
    )
    (net (code "21") (name "Net-(IC3-~{2Q})") (class "Default")
      (node (ref "IC3") (pin "6") (pinfunction "~{2Q}_6") (pintype "bidirectional"))
      (node (ref "JMP2") (pin "1") (pinfunction "1_1") (pintype "passive"))
    )
    (net (code "22") (name "Net-(IC4-~{1CP})") (class "Default")
      (node (ref "IC4") (pin "12") (pinfunction "~{1CP}_12") (pintype "bidirectional"))
      (node (ref "JMP_1") (pin "2") (pinfunction "2_2") (pintype "passive"))
    )
    (net (code "23") (name "Net-(IC4-~{1Q})") (class "Default")
      (node (ref "IC4") (pin "2") (pinfunction "~{1Q}_2") (pintype "bidirectional"))
      (node (ref "R3") (pin "2") (pinfunction "2_2") (pintype "passive"))
    )
    (net (code "24") (name "Net-(IC4-~{2CP})") (class "Default")
      (node (ref "IC4") (pin "9") (pinfunction "~{2CP}_9") (pintype "bidirectional"))
      (node (ref "JMP_") (pin "2") (pinfunction "2_2") (pintype "passive"))
    )
    (net (code "25") (name "Net-(IC4-~{2Q})") (class "Default")
      (node (ref "IC4") (pin "6") (pinfunction "~{2Q}_6") (pintype "bidirectional"))
      (node (ref "JMP_5") (pin "1") (pinfunction "1_1") (pintype "passive"))
      (node (ref "JMP_5") (pin "2") (pinfunction "2_2") (pintype "passive"))
      (node (ref "R16") (pin "2") (pinfunction "2_2") (pintype "passive"))
    )
    (net (code "26") (name "Net-(JMP-Pad1)") (class "Default")
      (node (ref "JMP") (pin "1") (pinfunction "1_1") (pintype "passive"))
      (node (ref "R11") (pin "1") (pinfunction "1_1") (pintype "passive"))
      (node (ref "S7") (pin "1") (pinfunction "1_1") (pintype "bidirectional"))
    )
    (net (code "27") (name "Net-(JMP2-Pad2)") (class "Default")
      (node (ref "JMP2") (pin "2") (pinfunction "2_2") (pintype "passive"))
      (node (ref "R15") (pin "2") (pinfunction "2_2") (pintype "passive"))
    )
    (net (code "28") (name "Net-(JMP3-Pad2)") (class "Default")
      (node (ref "JMP3") (pin "2") (pinfunction "2_2") (pintype "passive"))
      (node (ref "R10") (pin "2") (pinfunction "2_2") (pintype "passive"))
    )
    (net (code "29") (name "Net-(PAD2-P)") (class "Default")
      (node (ref "PAD2") (pin "1") (pinfunction "P_1") (pintype "passive"))
      (node (ref "R3") (pin "1") (pinfunction "1_1") (pintype "passive"))
    )
    (net (code "30") (name "Net-(PAD4-P)") (class "Default")
      (node (ref "PAD4") (pin "1") (pinfunction "P_1") (pintype "passive"))
      (node (ref "R10") (pin "1") (pinfunction "1_1") (pintype "passive"))
    )
    (net (code "31") (name "Net-(PAD6-P)") (class "Default")
      (node (ref "PAD6") (pin "1") (pinfunction "P_1") (pintype "passive"))
      (node (ref "R15") (pin "1") (pinfunction "1_1") (pintype "passive"))
    )
    (net (code "32") (name "Net-(PAD8-P)") (class "Default")
      (node (ref "PAD8") (pin "1") (pinfunction "P_1") (pintype "passive"))
      (node (ref "R16") (pin "1") (pinfunction "1_1") (pintype "passive"))
    )
    (net (code "33") (name "Net-(PAD10-P)") (class "Default")
      (node (ref "PAD10") (pin "1") (pinfunction "P_1") (pintype "passive"))
      (node (ref "R1") (pin "1") (pinfunction "1_1") (pintype "passive"))
    )
    (net (code "34") (name "Net-(PAD12-P)") (class "Default")
      (node (ref "PAD12") (pin "1") (pinfunction "P_1") (pintype "passive"))
      (node (ref "R8") (pin "1") (pinfunction "1_1") (pintype "passive"))
    )
    (net (code "35") (name "Net-(PAD13-P)") (class "Default")
      (node (ref "PAD13") (pin "1") (pinfunction "P_1") (pintype "passive"))
      (node (ref "R13") (pin "1") (pinfunction "1_1") (pintype "passive"))
    )
    (net (code "36") (name "REC{slash}PB") (class "Default")
      (node (ref "PAD32") (pin "1") (pinfunction "P_1") (pintype "passive"))
      (node (ref "R6") (pin "2") (pinfunction "2_2") (pintype "passive"))
      (node (ref "S5") (pin "1") (pinfunction "1_1") (pintype "bidirectional"))
    )
    (net (code "37") (name "SYNC") (class "Default")
      (node (ref "IC1") (pin "5") (pinfunction "2Q_5") (pintype "bidirectional"))
    )
    (net (code "38") (name "VCCIO") (class "Default")
      (node (ref "IC1") (pin "1") (pinfunction "1J_1") (pintype "bidirectional"))
      (node (ref "IC1") (pin "10") (pinfunction "~{2R}_10") (pintype "bidirectional"))
      (node (ref "IC1") (pin "11") (pinfunction "2K_11") (pintype "bidirectional"))
      (node (ref "IC1") (pin "13") (pinfunction "~{1R}_13") (pintype "bidirectional"))
      (node (ref "IC1") (pin "14") (pinfunction "VCC_14") (pintype "bidirectional"))
      (node (ref "IC1") (pin "4") (pinfunction "1K_4") (pintype "bidirectional"))
      (node (ref "IC1") (pin "8") (pinfunction "2J_8") (pintype "bidirectional"))
      (node (ref "IC2") (pin "1") (pinfunction "1J_1") (pintype "bidirectional"))
      (node (ref "IC2") (pin "10") (pinfunction "~{2R}_10") (pintype "bidirectional"))
      (node (ref "IC2") (pin "11") (pinfunction "2K_11") (pintype "bidirectional"))
      (node (ref "IC2") (pin "13") (pinfunction "~{1R}_13") (pintype "bidirectional"))
      (node (ref "IC2") (pin "14") (pinfunction "VCC_14") (pintype "bidirectional"))
      (node (ref "IC2") (pin "4") (pinfunction "1K_4") (pintype "bidirectional"))
      (node (ref "IC2") (pin "8") (pinfunction "2J_8") (pintype "bidirectional"))
      (node (ref "IC3") (pin "1") (pinfunction "1J_1") (pintype "bidirectional"))
      (node (ref "IC3") (pin "10") (pinfunction "~{2R}_10") (pintype "bidirectional"))
      (node (ref "IC3") (pin "11") (pinfunction "2K_11") (pintype "bidirectional"))
      (node (ref "IC3") (pin "13") (pinfunction "~{1R}_13") (pintype "bidirectional"))
      (node (ref "IC3") (pin "14") (pinfunction "VCC_14") (pintype "bidirectional"))
      (node (ref "IC3") (pin "4") (pinfunction "1K_4") (pintype "bidirectional"))
      (node (ref "IC3") (pin "8") (pinfunction "2J_8") (pintype "bidirectional"))
      (node (ref "IC4") (pin "1") (pinfunction "1J_1") (pintype "bidirectional"))
      (node (ref "IC4") (pin "10") (pinfunction "~{2R}_10") (pintype "bidirectional"))
      (node (ref "IC4") (pin "11") (pinfunction "2K_11") (pintype "bidirectional"))
      (node (ref "IC4") (pin "13") (pinfunction "~{1R}_13") (pintype "bidirectional"))
      (node (ref "IC4") (pin "14") (pinfunction "VCC_14") (pintype "bidirectional"))
      (node (ref "IC4") (pin "4") (pinfunction "1K_4") (pintype "bidirectional"))
      (node (ref "IC4") (pin "8") (pinfunction "2J_8") (pintype "bidirectional"))
      (node (ref "JMP_11") (pin "1") (pinfunction "1_1") (pintype "passive"))
      (node (ref "JMP_11") (pin "2") (pinfunction "2_2") (pintype "passive"))
      (node (ref "JMP_3") (pin "1") (pinfunction "1_1") (pintype "passive"))
      (node (ref "JMP_3") (pin "2") (pinfunction "2_2") (pintype "passive"))
      (node (ref "PAD1") (pin "1") (pinfunction "P_1") (pintype "passive"))
      (node (ref "PAD22") (pin "1") (pinfunction "P_1") (pintype "passive"))
      (node (ref "PAD3") (pin "1") (pinfunction "P_1") (pintype "passive"))
      (node (ref "PAD5") (pin "1") (pinfunction "P_1") (pintype "passive"))
      (node (ref "PAD7") (pin "1") (pinfunction "P_1") (pintype "passive"))
      (node (ref "R11") (pin "2") (pinfunction "2_2") (pintype "passive"))
      (node (ref "R12") (pin "2") (pinfunction "2_2") (pintype "passive"))
      (node (ref "R14") (pin "2") (pinfunction "2_2") (pintype "passive"))
      (node (ref "R2") (pin "2") (pinfunction "2_2") (pintype "passive"))
      (node (ref "R4") (pin "2") (pinfunction "2_2") (pintype "passive"))
      (node (ref "R6") (pin "1") (pinfunction "1_1") (pintype "passive"))
      (node (ref "R7") (pin "2") (pinfunction "2_2") (pintype "passive"))
      (node (ref "R9") (pin "2") (pinfunction "2_2") (pintype "passive"))
    )
    (net (code "39") (name "unconnected-(IC1-~{2CP}-Pad9)") (class "Default")
      (node (ref "IC1") (pin "9") (pinfunction "~{2CP}_9") (pintype "bidirectional"))
    )
    (net (code "40") (name "unconnected-(IC1-~{2Q}-Pad6)") (class "Default")
      (node (ref "IC1") (pin "6") (pinfunction "~{2Q}_6") (pintype "bidirectional"))
    )
    (net (code "41") (name "unconnected-(MP1-P$1-Pad1)") (class "Default")
      (node (ref "MP1") (pin "1") (pinfunction "P$1_1") (pintype "passive"))
    )
    (net (code "42") (name "unconnected-(MP2-P$1-Pad1)") (class "Default")
      (node (ref "MP2") (pin "1") (pinfunction "P$1_1") (pintype "passive"))
    )
    (net (code "43") (name "unconnected-(MP3-P$1-Pad1)") (class "Default")
      (node (ref "MP3") (pin "1") (pinfunction "P$1_1") (pintype "passive"))
    )
    (net (code "44") (name "unconnected-(MP4-P$1-Pad1)") (class "Default")
      (node (ref "MP4") (pin "1") (pinfunction "P$1_1") (pintype "passive"))
    )
    (net (code "45") (name "unconnected-(PAD17-P-Pad1)") (class "Default")
      (node (ref "PAD17") (pin "1") (pinfunction "P_1") (pintype "passive"))
    )
    (net (code "46") (name "unconnected-(PAD18-P-Pad1)") (class "Default")
      (node (ref "PAD18") (pin "1") (pinfunction "P_1") (pintype "passive"))
    )
    (net (code "47") (name "unconnected-(S1-PadMH1)") (class "Default")
      (node (ref "S1") (pin "MH1") (pinfunction "MH1_MH1") (pintype "bidirectional"))
    )
    (net (code "48") (name "unconnected-(S1-PadMH2)") (class "Default")
      (node (ref "S1") (pin "MH2") (pinfunction "MH2_MH2") (pintype "bidirectional"))
    )
    (net (code "49") (name "unconnected-(S2-PadMH1)") (class "Default")
      (node (ref "S2") (pin "MH1") (pinfunction "MH1_MH1") (pintype "bidirectional"))
    )
    (net (code "50") (name "unconnected-(S2-PadMH2)") (class "Default")
      (node (ref "S2") (pin "MH2") (pinfunction "MH2_MH2") (pintype "bidirectional"))
    )
    (net (code "51") (name "unconnected-(S4-PadMH1)") (class "Default")
      (node (ref "S4") (pin "MH1") (pinfunction "MH1_MH1") (pintype "bidirectional"))
    )
    (net (code "52") (name "unconnected-(S4-PadMH2)") (class "Default")
      (node (ref "S4") (pin "MH2") (pinfunction "MH2_MH2") (pintype "bidirectional"))
    )
    (net (code "53") (name "unconnected-(S5-PadMH1)") (class "Default")
      (node (ref "S5") (pin "MH1") (pinfunction "MH1_MH1") (pintype "bidirectional"))
    )
    (net (code "54") (name "unconnected-(S5-PadMH2)") (class "Default")
      (node (ref "S5") (pin "MH2") (pinfunction "MH2_MH2") (pintype "bidirectional"))
    )
    (net (code "55") (name "unconnected-(S6-PadMH1)") (class "Default")
      (node (ref "S6") (pin "MH1") (pinfunction "MH1_MH1") (pintype "bidirectional"))
    )
    (net (code "56") (name "unconnected-(S6-PadMH2)") (class "Default")
      (node (ref "S6") (pin "MH2") (pinfunction "MH2_MH2") (pintype "bidirectional"))
    )
    (net (code "57") (name "unconnected-(S7-PadMH1)") (class "Default")
      (node (ref "S7") (pin "MH1") (pinfunction "MH1_MH1") (pintype "bidirectional"))
    )
    (net (code "58") (name "unconnected-(S7-PadMH2)") (class "Default")
      (node (ref "S7") (pin "MH2") (pinfunction "MH2_MH2") (pintype "bidirectional"))
    )
    (net (code "59") (name "unconnected-(S8-PadMH1)") (class "Default")
      (node (ref "S8") (pin "MH1") (pinfunction "MH1_MH1") (pintype "bidirectional"))
    )
    (net (code "60") (name "unconnected-(S8-PadMH2)") (class "Default")
      (node (ref "S8") (pin "MH2") (pinfunction "MH2_MH2") (pintype "bidirectional"))
    )
    (net (code "61") (name "unconnected-(S9-PadMH1)") (class "Default")
      (node (ref "S9") (pin "MH1") (pinfunction "MH1_MH1") (pintype "bidirectional"))
    )
    (net (code "62") (name "unconnected-(S9-PadMH2)") (class "Default")
      (node (ref "S9") (pin "MH2") (pinfunction "MH2_MH2") (pintype "bidirectional"))
    )
  )
)
